# AccessControl.net
KiCad netlist of a schematic drawn in EAGLE
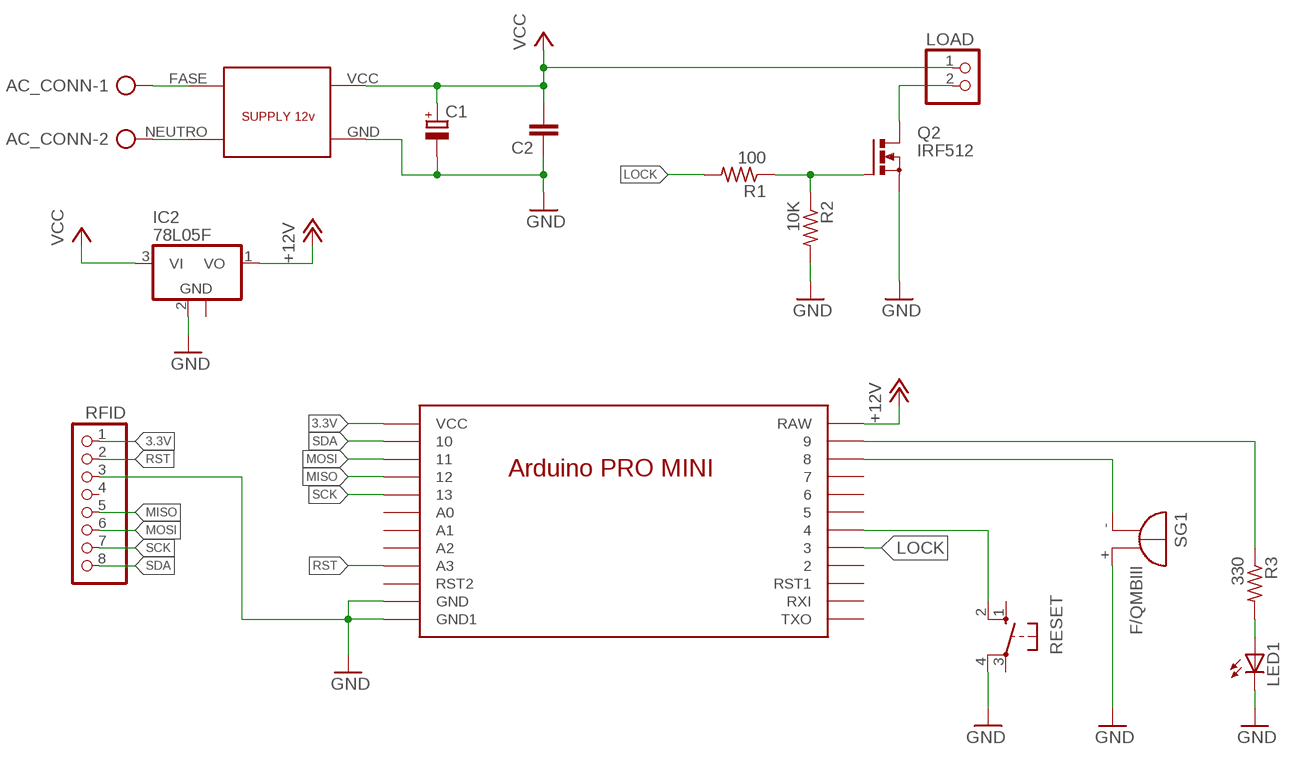
[diagram p0: schematic, sheet 1]

(export (version "E")
  (design (tool "Eeschema 10.0.6"))
  (components
    (comp (ref "AC_CONN")
      (value "AK300/2")
      (footprint "eagle-import:AK300_2")
      (libsource (lib "eagle-import") (part "AK300/2"))
    )
    (comp (ref "C1")
      (value "CPOL-EUE2.5-6")
      (footprint "eagle-import:E2,5-6")
      (libsource (lib "eagle-import") (part "CPOL-EUE2.5-6"))
    )
    (comp (ref "C2")
      (value "C2.5/2")
      (footprint "eagle-import:C2.5-2")
      (libsource (lib "eagle-import") (part "C2.5/2"))
    )
    (comp (ref "IC2")
      (value "78L05F")
      (footprint "eagle-import:SOT89")
      (libsource (lib "eagle-import") (part "78LF05"))
    )
    (comp (ref "LED1")
      (value "LED3MM")
      (footprint "eagle-import:LED3MM")
      (libsource (lib "eagle-import") (part "LED3MM"))
    )
    (comp (ref "LOAD")
      (value "PINHD-1X2")
      (footprint "eagle-import:1X02")
      (libsource (lib "eagle-import") (part "PINHD-1X2"))
    )
    (comp (ref "Q2")
      (value "IRF512")
      (footprint "eagle-import:TO220BV")
      (libsource (lib "eagle-import") (part "IRF512"))
    )
    (comp (ref "R1")
      (value "100")
      (footprint "eagle-import:0204_7")
      (libsource (lib "eagle-import") (part "R-US_0204/7"))
    )
    (comp (ref "R2")
      (value "10K")
      (footprint "eagle-import:0204_7")
      (libsource (lib "eagle-import") (part "R-US_0204/7"))
    )
    (comp (ref "R3")
      (value "330")
      (footprint "eagle-import:0204_7")
      (libsource (lib "eagle-import") (part "R-US_0204/7"))
    )
    (comp (ref "RESET")
      (value "10-XX")
      (footprint "eagle-import:B3F-10XX")
      (fields (field (name "MPN") "B3F-1000"))
      (libsource (lib "eagle-import") (part "10-XX"))
    )
    (comp (ref "RFID")
      (value "PINHD-1X8")
      (footprint "eagle-import:1X08")
      (libsource (lib "eagle-import") (part "PINHD-1X8"))
    )
    (comp (ref "SG1")
      (value "F/QMBIII")
      (footprint "eagle-import:F_QMBIII")
      (libsource (lib "eagle-import") (part "F/QMBIII"))
    )
    (comp (ref "U$1")
      (value "NANO")
      (footprint "eagle-import:NANO")
      (libsource (lib "eagle-import") (part "NANO"))
    )
    (comp (ref "U$2")
      (value "SUPPLY12V")
      (footprint "eagle-import:SUPPLY12V")
      (libsource (lib "eagle-import") (part "SUPPLY12V"))
    )
  )
  (nets
    (net (code "1") (name "+12V") (class "Default")
      (node (ref "IC2") (pin "1") (pinfunction "VO_1") (pintype "passive"))
      (node (ref "U$1") (pin "RAW") (pinfunction "RAW_RAW") (pintype "bidirectional"))
    )
    (net (code "2") (name "3.3V") (class "Default")
      (node (ref "RFID") (pin "1") (pinfunction "1_1") (pintype "passive"))
      (node (ref "U$1") (pin "VCC") (pinfunction "VCC_VCC") (pintype "bidirectional"))
    )
    (net (code "3") (name "GND") (class "Default")
      (node (ref "C1") (pin "-") (pinfunction "-_-") (pintype "passive"))
      (node (ref "C2") (pin "1") (pinfunction "1_1") (pintype "passive"))
      (node (ref "IC2") (pin "2") (pinfunction "GND_2") (pintype "passive"))
      (node (ref "LED1") (pin "K") (pinfunction "C_K") (pintype "passive"))
      (node (ref "Q2") (pin "S") (pinfunction "S_S") (pintype "passive"))
      (node (ref "R2") (pin "2") (pinfunction "2_2") (pintype "passive"))
      (node (ref "RESET") (pin "4") (pinfunction "P1_4") (pintype "passive"))
      (node (ref "RFID") (pin "3") (pinfunction "3_3") (pintype "passive"))
      (node (ref "SG1") (pin "+") (pinfunction "-_+") (pintype "passive"))
      (node (ref "U$1") (pin "GND1") (pinfunction "GND_GND1") (pintype "bidirectional"))
      (node (ref "U$1") (pin "GND2") (pinfunction "GND1_GND2") (pintype "power_in"))
      (node (ref "U$2") (pin "GND") (pinfunction "GND_GND") (pintype "bidirectional"))
    )
    (net (code "4") (name "LOCK") (class "Default")
      (node (ref "R1") (pin "2") (pinfunction "2_2") (pintype "passive"))
      (node (ref "U$1") (pin "3") (pinfunction "3_3") (pintype "bidirectional"))
    )
    (net (code "5") (name "MISO") (class "Default")
      (node (ref "RFID") (pin "5") (pinfunction "5_5") (pintype "passive"))
      (node (ref "U$1") (pin "12") (pinfunction "12_12") (pintype "bidirectional"))
    )
    (net (code "6") (name "MOSI") (class "Default")
      (node (ref "RFID") (pin "6") (pinfunction "6_6") (pintype "passive"))
      (node (ref "U$1") (pin "11") (pinfunction "11_11") (pintype "bidirectional"))
    )
    (net (code "7") (name "Net-(AC_CONNA-KL)") (class "Default")
      (node (ref "AC_CONN") (pin "1") (pinfunction "KL_1") (pintype "passive"))
      (node (ref "U$2") (pin "FASE") (pinfunction "FASE_FASE") (pintype "bidirectional"))
    )
    (net (code "8") (name "Net-(AC_CONNB-KL)") (class "Default")
      (node (ref "AC_CONN") (pin "2") (pinfunction "KL_2") (pintype "passive"))
      (node (ref "U$2") (pin "NEUTRO") (pinfunction "NEUTRO_NEUTRO") (pintype "bidirectional"))
    )
    (net (code "9") (name "Net-(LED1-PadA)") (class "Default")
      (node (ref "LED1") (pin "A") (pinfunction "A_A") (pintype "passive"))
      (node (ref "R3") (pin "2") (pinfunction "2_2") (pintype "passive"))
    )
    (net (code "10") (name "Net-(LOAD-Pad2)") (class "Default")
      (node (ref "LOAD") (pin "2") (pinfunction "2_2") (pintype "passive"))
      (node (ref "Q2") (pin "D") (pinfunction "D_D") (pintype "passive"))
    )
    (net (code "11") (name "Net-(Q2-PadG)") (class "Default")
      (node (ref "Q2") (pin "G") (pinfunction "G_G") (pintype "passive"))
      (node (ref "R1") (pin "1") (pinfunction "1_1") (pintype "passive"))
      (node (ref "R2") (pin "1") (pinfunction "1_1") (pintype "passive"))
    )
    (net (code "12") (name "Net-(R3-Pad1)") (class "Default")
      (node (ref "R3") (pin "1") (pinfunction "1_1") (pintype "passive"))
      (node (ref "U$1") (pin "9") (pinfunction "9_9") (pintype "bidirectional"))
    )
    (net (code "13") (name "Net-(RESET-S1)") (class "Default")
      (node (ref "RESET") (pin "2") (pinfunction "S1_2") (pintype "passive"))
      (node (ref "U$1") (pin "4") (pinfunction "4_4") (pintype "bidirectional"))
    )
    (net (code "14") (name "Net-(SG1-+)") (class "Default")
      (node (ref "SG1") (pin "-") (pinfunction "+_-") (pintype "passive"))
      (node (ref "U$1") (pin "8") (pinfunction "8_8") (pintype "bidirectional"))
    )
    (net (code "15") (name "RST") (class "Default")
      (node (ref "RFID") (pin "2") (pinfunction "2_2") (pintype "passive"))
      (node (ref "U$1") (pin "A3") (pinfunction "A3_A3") (pintype "bidirectional"))
    )
    (net (code "16") (name "SCK") (class "Default")
      (node (ref "RFID") (pin "7") (pinfunction "7_7") (pintype "passive"))
      (node (ref "U$1") (pin "13") (pinfunction "13_13") (pintype "bidirectional"))
    )
    (net (code "17") (name "SDA") (class "Default")
      (node (ref "RFID") (pin "8") (pinfunction "8_8") (pintype "passive"))
      (node (ref "U$1") (pin "10") (pinfunction "10_10") (pintype "bidirectional"))
    )
    (net (code "18") (name "VCC") (class "Default")
      (node (ref "C1") (pin "+") (pinfunction "+_+") (pintype "passive"))
      (node (ref "C2") (pin "2") (pinfunction "2_2") (pintype "passive"))
      (node (ref "IC2") (pin "3") (pinfunction "VI_3") (pintype "input"))
      (node (ref "LOAD") (pin "1") (pinfunction "1_1") (pintype "passive"))
      (node (ref "U$2") (pin "VCC") (pinfunction "VCC_VCC") (pintype "bidirectional"))
    )
    (net (code "19") (name "unconnected-(IC2-GND-Pad2@1)") (class "Default")
      (node (ref "IC2") (pin "2@1") (pinfunction "GND_2@1") (pintype "passive"))
    )
    (net (code "20") (name "unconnected-(RESET-P-Pad3)") (class "Default")
      (node (ref "RESET") (pin "3") (pinfunction "P_3") (pintype "passive"))
    )
    (net (code "21") (name "unconnected-(RESET-S-Pad1)") (class "Default")
      (node (ref "RESET") (pin "1") (pinfunction "S_1") (pintype "passive"))
    )
    (net (code "22") (name "unconnected-(RFID-Pad4)") (class "Default")
      (node (ref "RFID") (pin "4") (pinfunction "4_4") (pintype "passive"))
    )
    (net (code "23") (name "unconnected-(U$1-Pad2)") (class "Default")
      (node (ref "U$1") (pin "2") (pinfunction "2_2") (pintype "bidirectional"))
    )
    (net (code "24") (name "unconnected-(U$1-Pad5)") (class "Default")
      (node (ref "U$1") (pin "5") (pinfunction "5_5") (pintype "bidirectional"))
    )
    (net (code "25") (name "unconnected-(U$1-Pad6)") (class "Default")
      (node (ref "U$1") (pin "6") (pinfunction "6_6") (pintype "bidirectional"))
    )
    (net (code "26") (name "unconnected-(U$1-Pad7)") (class "Default")
      (node (ref "U$1") (pin "7") (pinfunction "7_7") (pintype "bidirectional"))
    )
    (net (code "27") (name "unconnected-(U$1-PadA0)") (class "Default")
      (node (ref "U$1") (pin "A0") (pinfunction "A0_A0") (pintype "bidirectional"))
    )
    (net (code "28") (name "unconnected-(U$1-PadA1)") (class "Default")
      (node (ref "U$1") (pin "A1") (pinfunction "A1_A1") (pintype "bidirectional"))
    )
    (net (code "29") (name "unconnected-(U$1-PadA2)") (class "Default")
      (node (ref "U$1") (pin "A2") (pinfunction "A2_A2") (pintype "bidirectional"))
    )
    (net (code "30") (name "unconnected-(U$1-PadRST1)") (class "Default")
      (node (ref "U$1") (pin "RST1") (pinfunction "RST1_RST1") (pintype "bidirectional"))
    )
    (net (code "31") (name "unconnected-(U$1-PadRST2)") (class "Default")
      (node (ref "U$1") (pin "RST2") (pinfunction "RST2_RST2") (pintype "bidirectional"))
    )
    (net (code "32") (name "unconnected-(U$1-PadRXI)") (class "Default")
      (node (ref "U$1") (pin "RXI") (pinfunction "RXI_RXI") (pintype "bidirectional"))
    )
    (net (code "33") (name "unconnected-(U$1-PadTXO)") (class "Default")
      (node (ref "U$1") (pin "TXO") (pinfunction "TXO_TXO") (pintype "bidirectional"))
    )
  )
)
